# Fan_testing_rig.net
KiCad netlist of a schematic drawn in EasyEDA
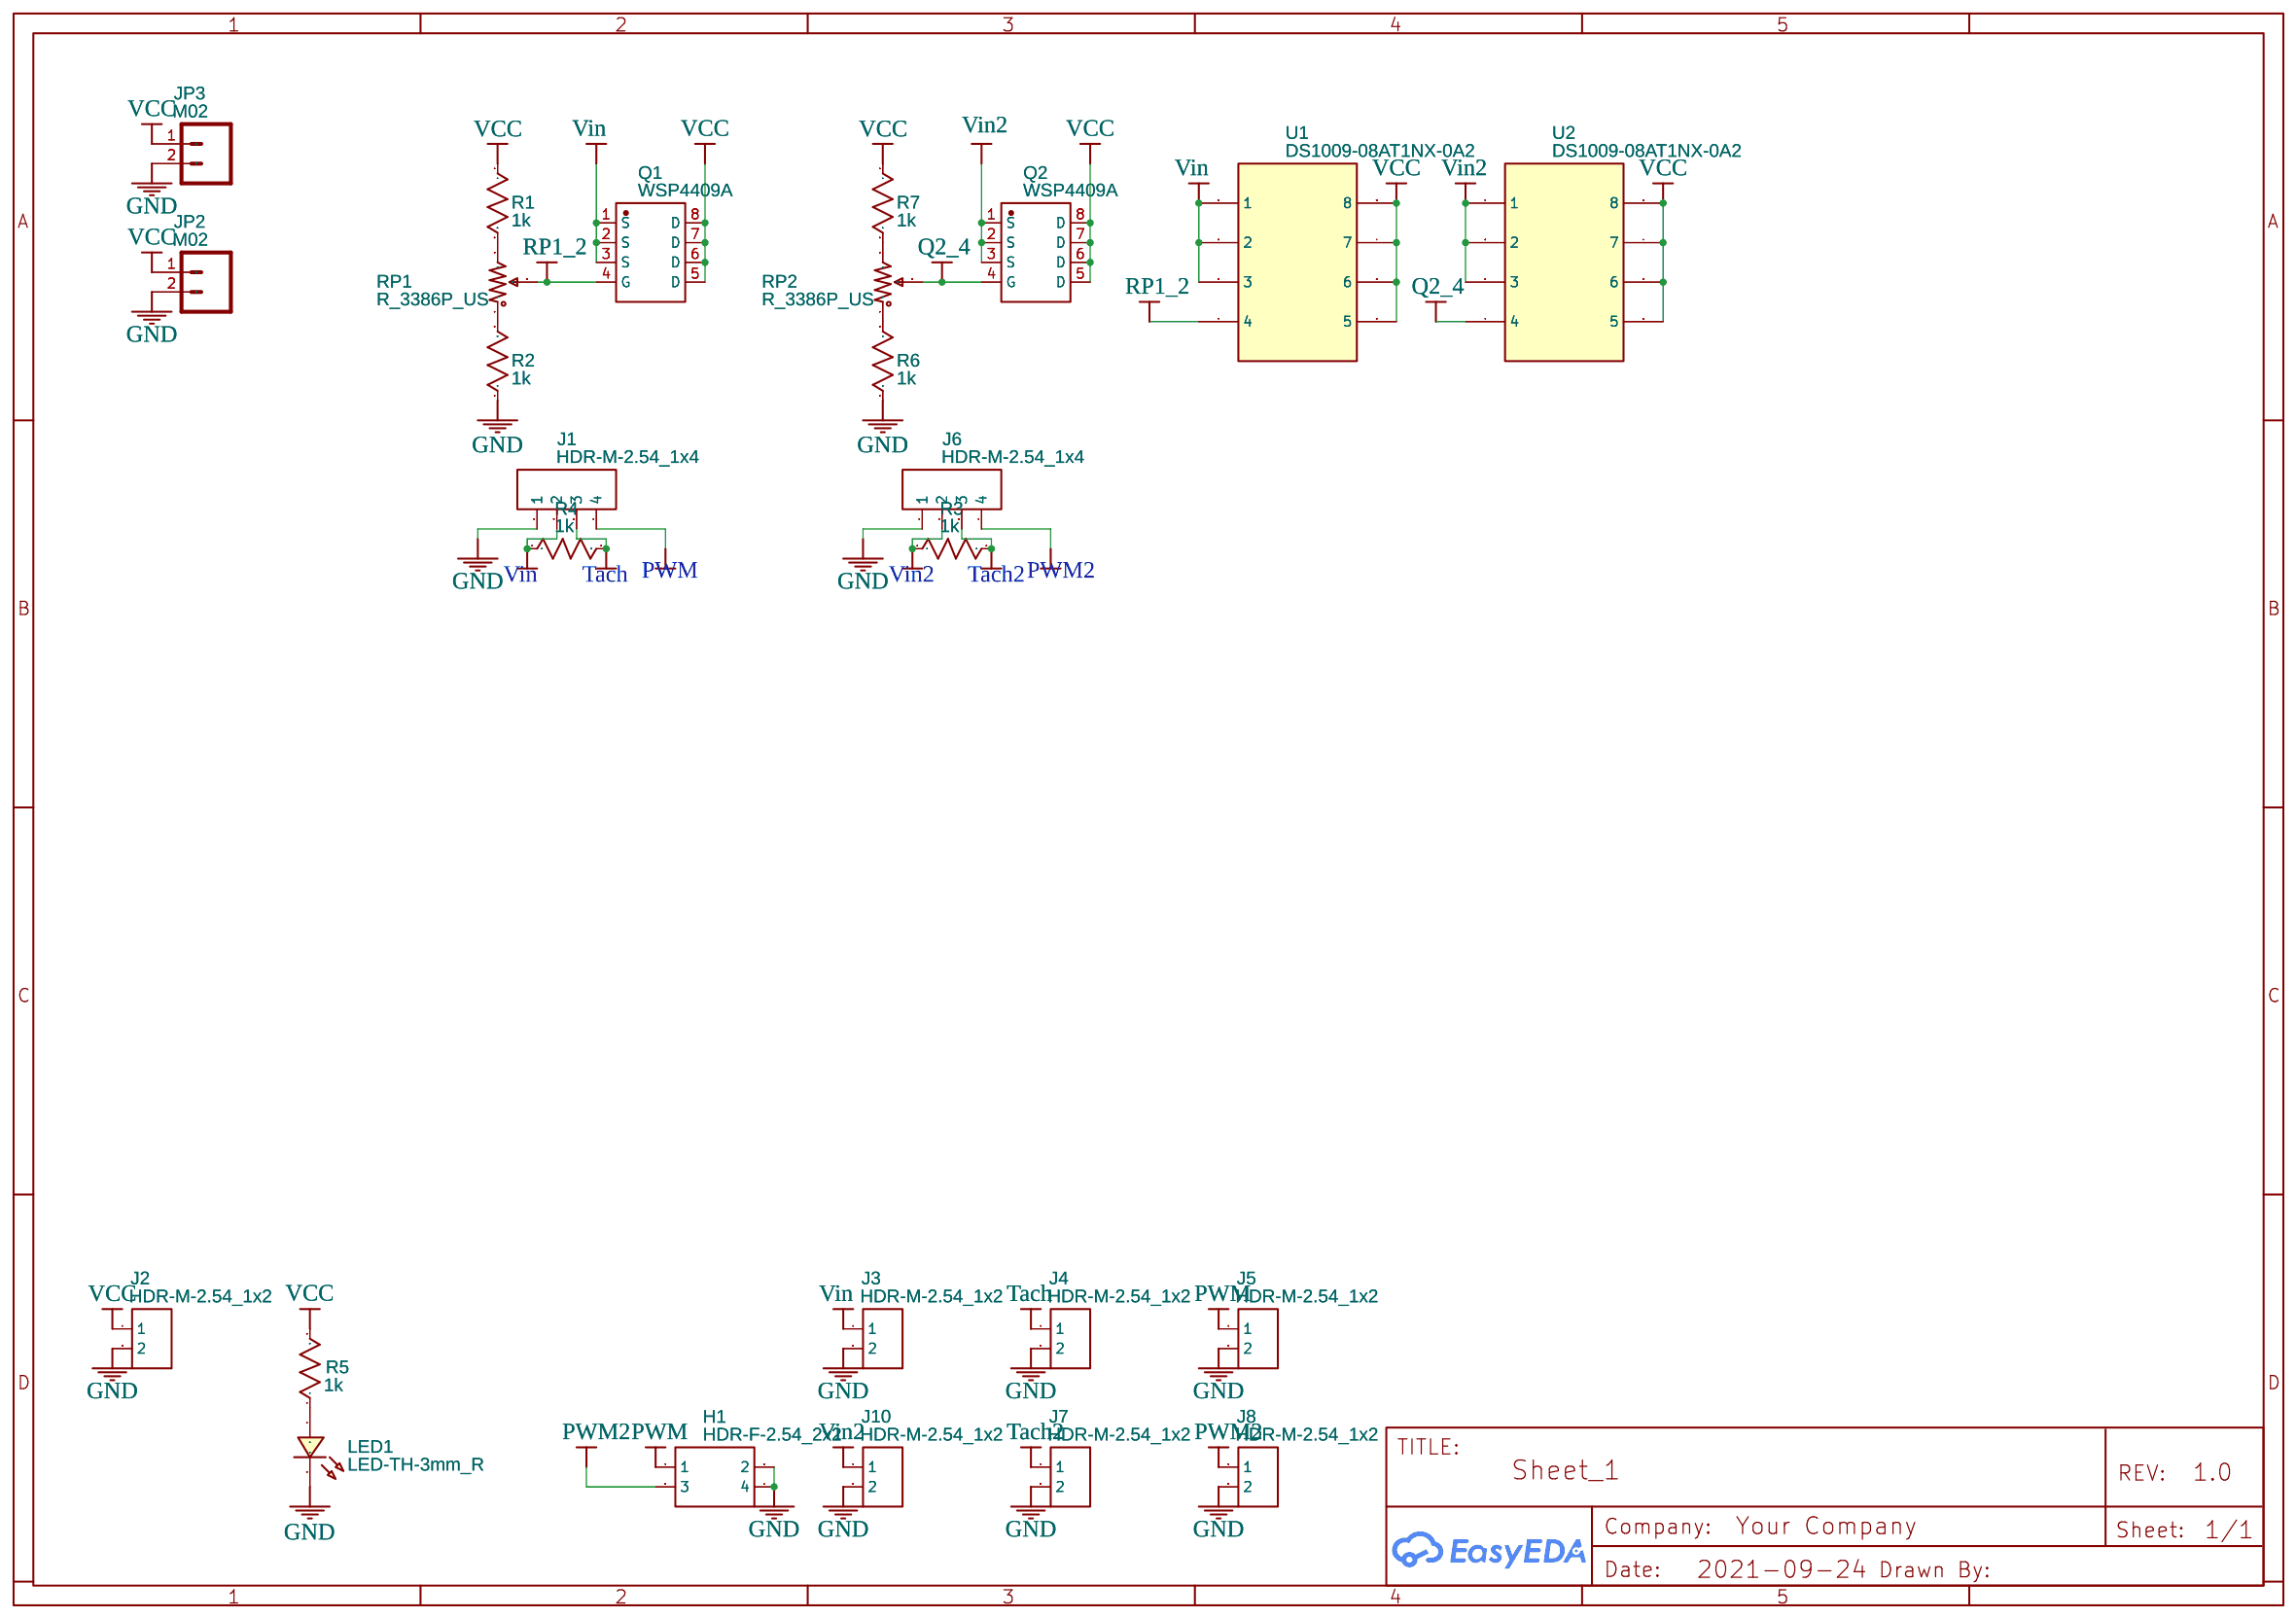
[diagram p0: main unit]
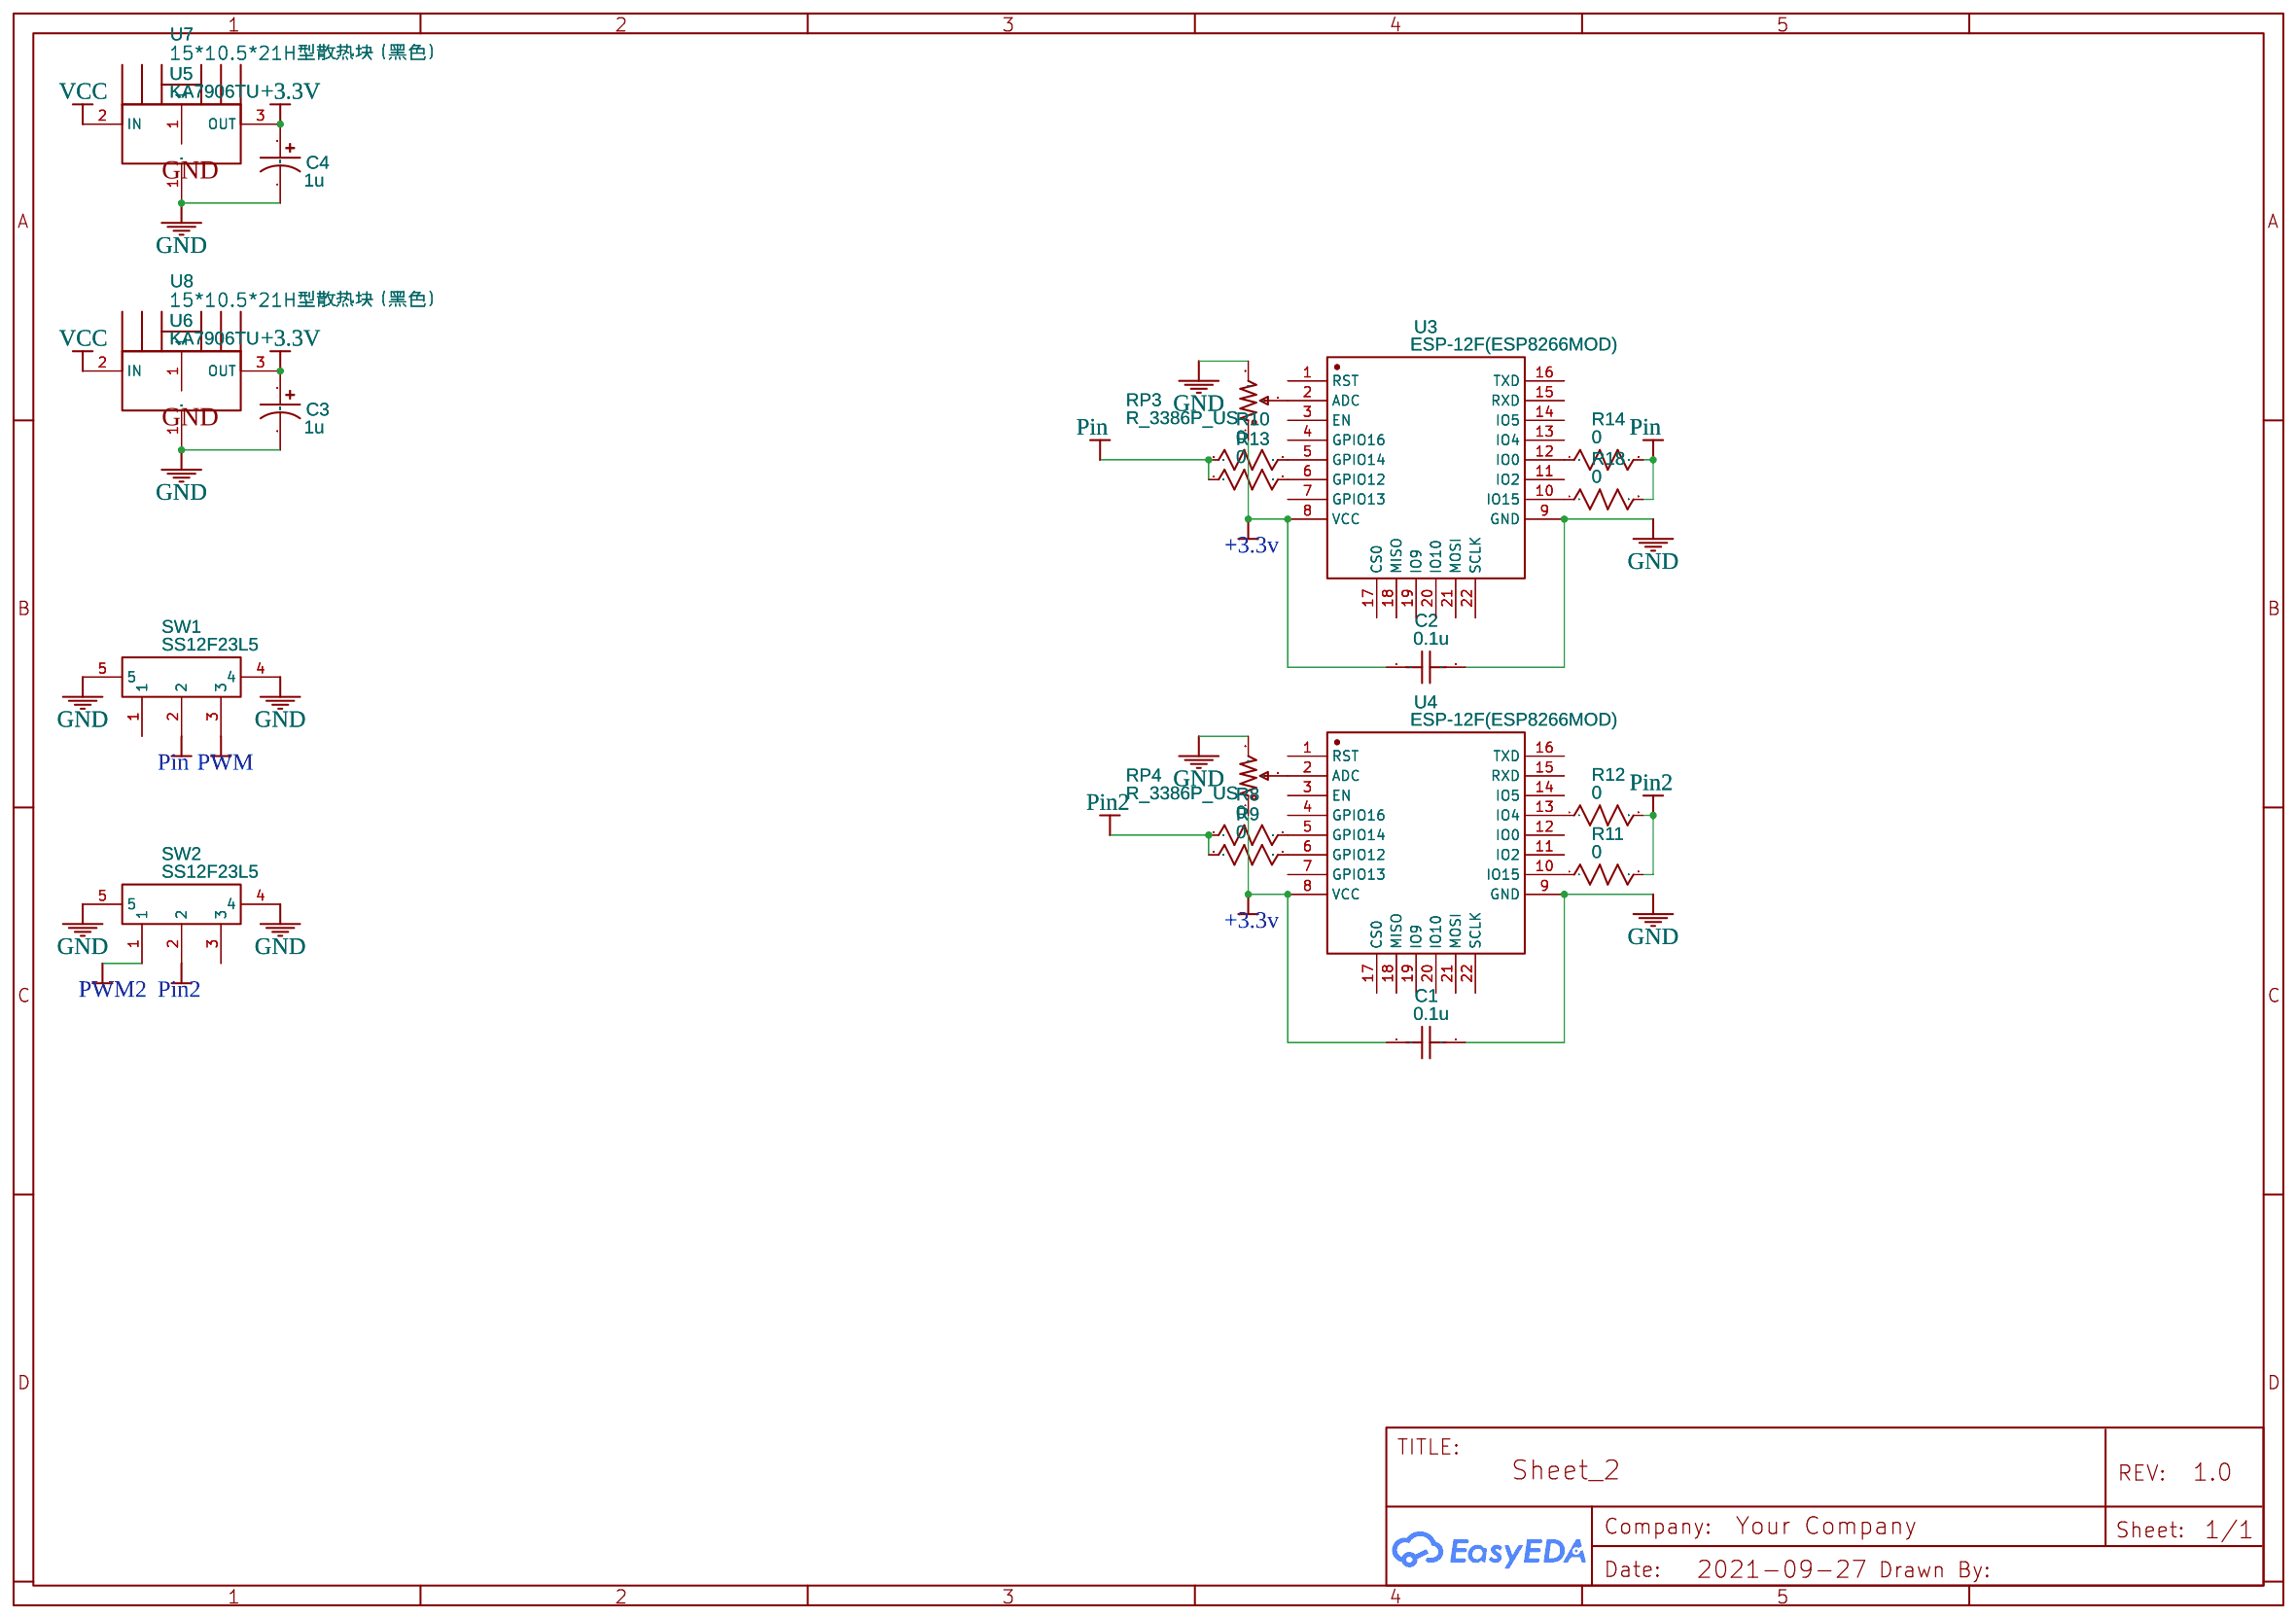
[diagram p1: PWM controll]

(export (version "E")
  (design (tool "Eeschema 10.0.6"))
  (components
    (comp (ref "H1")
      (value "HDR-F-2.54_2x2")
      (fields (field (name "BOM_Supplier Part") "C239342"))
      (libsource (lib "") (part "HDR-F-2.54_2x2"))
    )
    (comp (ref "J1")
      (value "HDR-M-2.54_1x4")
      (fields (field (name "BOM_Supplier Part") "C124378"))
      (libsource (lib "") (part "HDR-M-2.54_1x4"))
    )
    (comp (ref "J2")
      (value "HDR-M-2.54_1x2")
      (fields (field (name "BOM_Supplier Part") "C124375"))
      (libsource (lib "") (part "HDR-M-2.54_1x2"))
    )
    (comp (ref "J3")
      (value "HDR-M-2.54_1x2")
      (fields (field (name "BOM_Supplier Part") "C124375"))
      (libsource (lib "") (part "HDR-M-2.54_1x2"))
    )
    (comp (ref "J4")
      (value "HDR-M-2.54_1x2")
      (fields (field (name "BOM_Supplier Part") "C124375"))
      (libsource (lib "") (part "HDR-M-2.54_1x2"))
    )
    (comp (ref "J5")
      (value "HDR-M-2.54_1x2")
      (fields (field (name "BOM_Supplier Part") "C124375"))
      (libsource (lib "") (part "HDR-M-2.54_1x2"))
    )
    (comp (ref "J6")
      (value "HDR-M-2.54_1x4")
      (fields (field (name "BOM_Supplier Part") "C124378"))
      (libsource (lib "") (part "HDR-M-2.54_1x4"))
    )
    (comp (ref "J7")
      (value "HDR-M-2.54_1x2")
      (fields (field (name "BOM_Supplier Part") "C124375"))
      (libsource (lib "") (part "HDR-M-2.54_1x2"))
    )
    (comp (ref "J8")
      (value "HDR-M-2.54_1x2")
      (fields (field (name "BOM_Supplier Part") "C124375"))
      (libsource (lib "") (part "HDR-M-2.54_1x2"))
    )
    (comp (ref "J10")
      (value "HDR-M-2.54_1x2")
      (fields (field (name "BOM_Supplier Part") "C124375"))
      (libsource (lib "") (part "HDR-M-2.54_1x2"))
    )
    (comp (ref "JP2") (value "M02") (libsource (lib "") (part "M02")))
    (comp (ref "JP3") (value "M02") (libsource (lib "") (part "M02")))
    (comp (ref "LED1")
      (value "LED-TH-3mm_R")
      (fields
        (field (name "BOM_Manufacturer Part") "204-10SDRD/S530-A3-L")
        (field (name "BOM_Supplier Part") "C84774")
      )
      (libsource (lib "") (part "LED-TH-3mm_R"))
    )
    (comp (ref "Q1")
      (value "WSP4409A")
      (fields (field (name "BOM_Supplier Part") "C2880527"))
      (libsource (lib "") (part "WSP4409A"))
    )
    (comp (ref "Q2")
      (value "WSP4409A")
      (fields (field (name "BOM_Supplier Part") "C2880527"))
      (libsource (lib "") (part "WSP4409A"))
    )
    (comp (ref "R1") (value "1k") (libsource (lib "") (part "R_AXIAL-0.3_US")))
    (comp (ref "R2") (value "1k") (libsource (lib "") (part "R_AXIAL-0.3_US_1")))
    (comp (ref "R3") (value "1k") (libsource (lib "") (part "R_AXIAL-0.3_US_2")))
    (comp (ref "R4") (value "1k") (libsource (lib "") (part "R_AXIAL-0.3_US_2")))
    (comp (ref "R5") (value "1k") (libsource (lib "") (part "R_AXIAL-0.3_US_1")))
    (comp (ref "R6") (value "1k") (libsource (lib "") (part "R_AXIAL-0.3_US_1")))
    (comp (ref "R7") (value "1k") (libsource (lib "") (part "R_AXIAL-0.3_US")))
    (comp (ref "RP1") (value "R_3386P_US") (libsource (lib "") (part "R_3386P_US")))
    (comp (ref "RP2") (value "R_3386P_US") (libsource (lib "") (part "R_3386P_US")))
    (comp (ref "U1")
      (value "DS1009-08AT1NX-0A2")
      (fields (field (name "BOM_Supplier Part") "C72124"))
      (libsource (lib "") (part "DS1009-08AT1NX-0A2"))
    )
    (comp (ref "U2")
      (value "DS1009-08AT1NX-0A2")
      (fields (field (name "BOM_Supplier Part") "C72124"))
      (libsource (lib "") (part "DS1009-08AT1NX-0A2"))
    )
    (comp (ref "C1") (value "0.1u") (libsource (lib "") (part "C_0805_US")))
    (comp (ref "C2") (value "0.1u") (libsource (lib "") (part "C_0805_US")))
    (comp (ref "C3") (value "1u") (libsource (lib "") (part "CE_TH_D8.0×F3.5_US")))
    (comp (ref "C4") (value "1u") (libsource (lib "") (part "CE_TH_D8.0×F3.5_US")))
    (comp (ref "R8") (value "0") (libsource (lib "") (part "R_AXIAL-0.3_US")))
    (comp (ref "R9") (value "0") (libsource (lib "") (part "R_AXIAL-0.3_US")))
    (comp (ref "R10") (value "0") (libsource (lib "") (part "R_AXIAL-0.3_US")))
    (comp (ref "R11") (value "0") (libsource (lib "") (part "R_AXIAL-0.3_US")))
    (comp (ref "R12") (value "0") (libsource (lib "") (part "R_AXIAL-0.3_US")))
    (comp (ref "R13") (value "0") (libsource (lib "") (part "R_AXIAL-0.3_US")))
    (comp (ref "R14") (value "0") (libsource (lib "") (part "R_AXIAL-0.3_US")))
    (comp (ref "R18") (value "0") (libsource (lib "") (part "R_AXIAL-0.3_US")))
    (comp (ref "RP3") (value "R_3386P_US") (libsource (lib "") (part "R_3386P_US")))
    (comp (ref "RP4") (value "R_3386P_US") (libsource (lib "") (part "R_3386P_US")))
    (comp (ref "SW1")
      (value "SS12F23L5")
      (fields (field (name "BOM_Supplier Part") "C2884749"))
      (libsource (lib "") (part "SS12F23L5"))
    )
    (comp (ref "SW2")
      (value "SS12F23L5")
      (fields (field (name "BOM_Supplier Part") "C2884749"))
      (libsource (lib "") (part "SS12F23L5"))
    )
    (comp (ref "U3")
      (value "ESP-12F(ESP8266MOD)")
      (fields (field (name "BOM_Supplier Part") "C82891"))
      (libsource (lib "") (part "ESP-12F(ESP8266MOD)"))
    )
    (comp (ref "U4")
      (value "ESP-12F(ESP8266MOD)")
      (fields (field (name "BOM_Supplier Part") "C82891"))
      (libsource (lib "") (part "ESP-12F(ESP8266MOD)"))
    )
    (comp (ref "U5")
      (value "KA7906TU")
      (fields (field (name "BOM_Supplier Part") "C112610"))
      (libsource (lib "") (part "KA7906TU"))
    )
    (comp (ref "U6")
      (value "KA7906TU")
      (fields (field (name "BOM_Supplier Part") "C112610"))
      (libsource (lib "") (part "KA7906TU"))
    )
    (comp (ref "U7")
      (value "15*10.5*21H型散热块（黑色）")
      (fields (field (name "BOM_Supplier Part") "C116600"))
      (libsource (lib "") (part "15*10.5*21H型散热块（黑色）"))
    )
    (comp (ref "U8")
      (value "15*10.5*21H型散热块（黑色）")
      (fields (field (name "BOM_Supplier Part") "C116600"))
      (libsource (lib "") (part "15*10.5*21H型散热块（黑色）"))
    )
  )
  (nets
    (net (code "1") (name "+3.3V") (class "Default")
      (node (ref "C3") (pin "1") (pinfunction "1_1") (pintype "unspecified"))
      (node (ref "C4") (pin "1") (pinfunction "1_1") (pintype "unspecified"))
      (node (ref "U5") (pin "3") (pinfunction "OUT_3") (pintype "passive"))
      (node (ref "U6") (pin "3") (pinfunction "OUT_3") (pintype "passive"))
    )
    (net (code "2") (name "+3.3v") (class "Default")
      (node (ref "C1") (pin "1") (pinfunction "1_1") (pintype "unspecified"))
      (node (ref "C2") (pin "1") (pinfunction "1_1") (pintype "unspecified"))
      (node (ref "RP3") (pin "1") (pinfunction "1_1") (pintype "unspecified"))
      (node (ref "RP4") (pin "1") (pinfunction "1_1") (pintype "unspecified"))
      (node (ref "U3") (pin "8") (pinfunction "VCC_8") (pintype "unspecified"))
      (node (ref "U4") (pin "8") (pinfunction "VCC_8") (pintype "unspecified"))
    )
    (net (code "3") (name "GND") (class "Default")
      (node (ref "C1") (pin "2") (pinfunction "2_2") (pintype "unspecified"))
      (node (ref "C2") (pin "2") (pinfunction "2_2") (pintype "unspecified"))
      (node (ref "C3") (pin "2") (pinfunction "2_2") (pintype "unspecified"))
      (node (ref "C4") (pin "2") (pinfunction "2_2") (pintype "unspecified"))
      (node (ref "H1") (pin "2") (pinfunction "2_2") (pintype "unspecified"))
      (node (ref "H1") (pin "4") (pinfunction "4_4") (pintype "unspecified"))
      (node (ref "J1") (pin "1") (pinfunction "1_1") (pintype "unspecified"))
      (node (ref "J10") (pin "2") (pinfunction "2_2") (pintype "unspecified"))
      (node (ref "J2") (pin "2") (pinfunction "2_2") (pintype "unspecified"))
      (node (ref "J3") (pin "2") (pinfunction "2_2") (pintype "unspecified"))
      (node (ref "J4") (pin "2") (pinfunction "2_2") (pintype "unspecified"))
      (node (ref "J5") (pin "2") (pinfunction "2_2") (pintype "unspecified"))
      (node (ref "J6") (pin "1") (pinfunction "1_1") (pintype "unspecified"))
      (node (ref "J7") (pin "2") (pinfunction "2_2") (pintype "unspecified"))
      (node (ref "J8") (pin "2") (pinfunction "2_2") (pintype "unspecified"))
      (node (ref "JP2") (pin "2") (pinfunction "2_2") (pintype "unspecified"))
      (node (ref "JP3") (pin "2") (pinfunction "2_2") (pintype "unspecified"))
      (node (ref "LED1") (pin "2") (pinfunction "2_2") (pintype "unspecified"))
      (node (ref "R2") (pin "1") (pinfunction "1_1") (pintype "unspecified"))
      (node (ref "R6") (pin "1") (pinfunction "1_1") (pintype "unspecified"))
      (node (ref "RP3") (pin "3") (pinfunction "3_3") (pintype "unspecified"))
      (node (ref "RP4") (pin "3") (pinfunction "3_3") (pintype "unspecified"))
      (node (ref "SW1") (pin "4") (pinfunction "4_4") (pintype "unspecified"))
      (node (ref "SW1") (pin "5") (pinfunction "5_5") (pintype "unspecified"))
      (node (ref "SW2") (pin "4") (pinfunction "4_4") (pintype "unspecified"))
      (node (ref "SW2") (pin "5") (pinfunction "5_5") (pintype "unspecified"))
      (node (ref "U3") (pin "9") (pinfunction "GND_9") (pintype "unspecified"))
      (node (ref "U4") (pin "9") (pinfunction "GND_9") (pintype "unspecified"))
      (node (ref "U5") (pin "1") (pinfunction "GND_1") (pintype "passive"))
      (node (ref "U6") (pin "1") (pinfunction "GND_1") (pintype "passive"))
    )
    (net (code "4") (name "Net-(LED1-Pad1)") (class "Default")
      (node (ref "LED1") (pin "1") (pinfunction "1_1") (pintype "unspecified"))
      (node (ref "R5") (pin "1") (pinfunction "1_1") (pintype "unspecified"))
    )
    (net (code "5") (name "Net-(R1-Pad2)") (class "Default")
      (node (ref "R1") (pin "2") (pinfunction "2_2") (pintype "unspecified"))
      (node (ref "RP1") (pin "3") (pinfunction "3_3") (pintype "unspecified"))
    )
    (net (code "6") (name "Net-(R2-Pad2)") (class "Default")
      (node (ref "R2") (pin "2") (pinfunction "2_2") (pintype "unspecified"))
      (node (ref "RP1") (pin "1") (pinfunction "1_1") (pintype "unspecified"))
    )
    (net (code "7") (name "Net-(R6-Pad2)") (class "Default")
      (node (ref "R6") (pin "2") (pinfunction "2_2") (pintype "unspecified"))
      (node (ref "RP2") (pin "1") (pinfunction "1_1") (pintype "unspecified"))
    )
    (net (code "8") (name "Net-(R7-Pad2)") (class "Default")
      (node (ref "R7") (pin "2") (pinfunction "2_2") (pintype "unspecified"))
      (node (ref "RP2") (pin "3") (pinfunction "3_3") (pintype "unspecified"))
    )
    (net (code "9") (name "Net-(U3-ADC)") (class "Default")
      (node (ref "RP3") (pin "2") (pinfunction "2_2") (pintype "unspecified"))
      (node (ref "U3") (pin "2") (pinfunction "ADC_2") (pintype "unspecified"))
    )
    (net (code "10") (name "Net-(U3-GPIO12)") (class "Default")
      (node (ref "R13") (pin "2") (pinfunction "2_2") (pintype "unspecified"))
      (node (ref "U3") (pin "6") (pinfunction "GPIO12_6") (pintype "unspecified"))
    )
    (net (code "11") (name "Net-(U3-GPIO14)") (class "Default")
      (node (ref "R10") (pin "2") (pinfunction "2_2") (pintype "unspecified"))
      (node (ref "U3") (pin "5") (pinfunction "GPIO14_5") (pintype "unspecified"))
    )
    (net (code "12") (name "Net-(U3-IO0)") (class "Default")
      (node (ref "R14") (pin "1") (pinfunction "1_1") (pintype "unspecified"))
      (node (ref "U3") (pin "12") (pinfunction "IO0_12") (pintype "unspecified"))
    )
    (net (code "13") (name "Net-(U3-IO15)") (class "Default")
      (node (ref "R18") (pin "1") (pinfunction "1_1") (pintype "unspecified"))
      (node (ref "U3") (pin "10") (pinfunction "IO15_10") (pintype "unspecified"))
    )
    (net (code "14") (name "Net-(U4-ADC)") (class "Default")
      (node (ref "RP4") (pin "2") (pinfunction "2_2") (pintype "unspecified"))
      (node (ref "U4") (pin "2") (pinfunction "ADC_2") (pintype "unspecified"))
    )
    (net (code "15") (name "Net-(U4-GPIO12)") (class "Default")
      (node (ref "R9") (pin "2") (pinfunction "2_2") (pintype "unspecified"))
      (node (ref "U4") (pin "6") (pinfunction "GPIO12_6") (pintype "unspecified"))
    )
    (net (code "16") (name "Net-(U4-GPIO14)") (class "Default")
      (node (ref "R8") (pin "2") (pinfunction "2_2") (pintype "unspecified"))
      (node (ref "U4") (pin "5") (pinfunction "GPIO14_5") (pintype "unspecified"))
    )
    (net (code "17") (name "Net-(U4-IO4)") (class "Default")
      (node (ref "R12") (pin "1") (pinfunction "1_1") (pintype "unspecified"))
      (node (ref "U4") (pin "13") (pinfunction "IO4_13") (pintype "unspecified"))
    )
    (net (code "18") (name "Net-(U4-IO15)") (class "Default")
      (node (ref "R11") (pin "1") (pinfunction "1_1") (pintype "unspecified"))
      (node (ref "U4") (pin "10") (pinfunction "IO15_10") (pintype "unspecified"))
    )
    (net (code "19") (name "PWM") (class "Default")
      (node (ref "H1") (pin "1") (pinfunction "1_1") (pintype "unspecified"))
      (node (ref "J1") (pin "4") (pinfunction "4_4") (pintype "unspecified"))
      (node (ref "J5") (pin "1") (pinfunction "1_1") (pintype "unspecified"))
      (node (ref "SW1") (pin "3") (pinfunction "3_3") (pintype "unspecified"))
    )
    (net (code "20") (name "PWM2") (class "Default")
      (node (ref "H1") (pin "3") (pinfunction "3_3") (pintype "unspecified"))
      (node (ref "J6") (pin "4") (pinfunction "4_4") (pintype "unspecified"))
      (node (ref "J8") (pin "1") (pinfunction "1_1") (pintype "unspecified"))
      (node (ref "SW2") (pin "1") (pinfunction "1_1") (pintype "unspecified"))
    )
    (net (code "21") (name "Pin") (class "Default")
      (node (ref "R10") (pin "1") (pinfunction "1_1") (pintype "unspecified"))
      (node (ref "R13") (pin "1") (pinfunction "1_1") (pintype "unspecified"))
      (node (ref "R14") (pin "2") (pinfunction "2_2") (pintype "unspecified"))
      (node (ref "R18") (pin "2") (pinfunction "2_2") (pintype "unspecified"))
      (node (ref "SW1") (pin "2") (pinfunction "2_2") (pintype "unspecified"))
    )
    (net (code "22") (name "Pin2") (class "Default")
      (node (ref "R11") (pin "2") (pinfunction "2_2") (pintype "unspecified"))
      (node (ref "R12") (pin "2") (pinfunction "2_2") (pintype "unspecified"))
      (node (ref "R8") (pin "1") (pinfunction "1_1") (pintype "unspecified"))
      (node (ref "R9") (pin "1") (pinfunction "1_1") (pintype "unspecified"))
      (node (ref "SW2") (pin "2") (pinfunction "2_2") (pintype "unspecified"))
    )
    (net (code "23") (name "Q2_4") (class "Default")
      (node (ref "Q2") (pin "4") (pinfunction "G_4") (pintype "unspecified"))
      (node (ref "RP2") (pin "2") (pinfunction "2_2") (pintype "unspecified"))
      (node (ref "U2") (pin "4") (pinfunction "4_4") (pintype "input"))
    )
    (net (code "24") (name "RP1_2") (class "Default")
      (node (ref "Q1") (pin "4") (pinfunction "G_4") (pintype "unspecified"))
      (node (ref "RP1") (pin "2") (pinfunction "2_2") (pintype "unspecified"))
      (node (ref "U1") (pin "4") (pinfunction "4_4") (pintype "input"))
    )
    (net (code "25") (name "Tach") (class "Default")
      (node (ref "J1") (pin "3") (pinfunction "3_3") (pintype "unspecified"))
      (node (ref "J4") (pin "1") (pinfunction "1_1") (pintype "unspecified"))
      (node (ref "R4") (pin "2") (pinfunction "2_2") (pintype "unspecified"))
    )
    (net (code "26") (name "Tach2") (class "Default")
      (node (ref "J6") (pin "3") (pinfunction "3_3") (pintype "unspecified"))
      (node (ref "J7") (pin "1") (pinfunction "1_1") (pintype "unspecified"))
      (node (ref "R3") (pin "2") (pinfunction "2_2") (pintype "unspecified"))
    )
    (net (code "27") (name "VCC") (class "Default")
      (node (ref "J2") (pin "1") (pinfunction "1_1") (pintype "unspecified"))
      (node (ref "JP2") (pin "1") (pinfunction "1_1") (pintype "unspecified"))
      (node (ref "JP3") (pin "1") (pinfunction "1_1") (pintype "unspecified"))
      (node (ref "Q1") (pin "5") (pinfunction "D_5") (pintype "unspecified"))
      (node (ref "Q1") (pin "6") (pinfunction "D_6") (pintype "unspecified"))
      (node (ref "Q1") (pin "7") (pinfunction "D_7") (pintype "unspecified"))
      (node (ref "Q1") (pin "8") (pinfunction "D_8") (pintype "unspecified"))
      (node (ref "Q2") (pin "5") (pinfunction "D_5") (pintype "unspecified"))
      (node (ref "Q2") (pin "6") (pinfunction "D_6") (pintype "unspecified"))
      (node (ref "Q2") (pin "7") (pinfunction "D_7") (pintype "unspecified"))
      (node (ref "Q2") (pin "8") (pinfunction "D_8") (pintype "unspecified"))
      (node (ref "R1") (pin "1") (pinfunction "1_1") (pintype "unspecified"))
      (node (ref "R5") (pin "2") (pinfunction "2_2") (pintype "unspecified"))
      (node (ref "R7") (pin "1") (pinfunction "1_1") (pintype "unspecified"))
      (node (ref "U1") (pin "5") (pinfunction "5_5") (pintype "input"))
      (node (ref "U1") (pin "6") (pinfunction "6_6") (pintype "input"))
      (node (ref "U1") (pin "7") (pinfunction "7_7") (pintype "input"))
      (node (ref "U1") (pin "8") (pinfunction "8_8") (pintype "input"))
      (node (ref "U2") (pin "5") (pinfunction "5_5") (pintype "input"))
      (node (ref "U2") (pin "6") (pinfunction "6_6") (pintype "input"))
      (node (ref "U2") (pin "7") (pinfunction "7_7") (pintype "input"))
      (node (ref "U2") (pin "8") (pinfunction "8_8") (pintype "input"))
      (node (ref "U5") (pin "2") (pinfunction "IN_2") (pintype "passive"))
      (node (ref "U6") (pin "2") (pinfunction "IN_2") (pintype "passive"))
    )
    (net (code "28") (name "Vin") (class "Default")
      (node (ref "J1") (pin "2") (pinfunction "2_2") (pintype "unspecified"))
      (node (ref "J3") (pin "1") (pinfunction "1_1") (pintype "unspecified"))
      (node (ref "Q1") (pin "1") (pinfunction "S_1") (pintype "unspecified"))
      (node (ref "Q1") (pin "2") (pinfunction "S_2") (pintype "unspecified"))
      (node (ref "Q1") (pin "3") (pinfunction "S_3") (pintype "unspecified"))
      (node (ref "R4") (pin "1") (pinfunction "1_1") (pintype "unspecified"))
      (node (ref "U1") (pin "1") (pinfunction "1_1") (pintype "input"))
      (node (ref "U1") (pin "2") (pinfunction "2_2") (pintype "input"))
      (node (ref "U1") (pin "3") (pinfunction "3_3") (pintype "input"))
    )
    (net (code "29") (name "Vin2") (class "Default")
      (node (ref "J10") (pin "1") (pinfunction "1_1") (pintype "unspecified"))
      (node (ref "J6") (pin "2") (pinfunction "2_2") (pintype "unspecified"))
      (node (ref "Q2") (pin "1") (pinfunction "S_1") (pintype "unspecified"))
      (node (ref "Q2") (pin "2") (pinfunction "S_2") (pintype "unspecified"))
      (node (ref "Q2") (pin "3") (pinfunction "S_3") (pintype "unspecified"))
      (node (ref "R3") (pin "1") (pinfunction "1_1") (pintype "unspecified"))
      (node (ref "U2") (pin "1") (pinfunction "1_1") (pintype "input"))
      (node (ref "U2") (pin "2") (pinfunction "2_2") (pintype "input"))
      (node (ref "U2") (pin "3") (pinfunction "3_3") (pintype "input"))
    )
    (net (code "30") (name "unconnected-(SW1-Pad1)") (class "Default")
      (node (ref "SW1") (pin "1") (pinfunction "1_1") (pintype "unspecified"))
    )
    (net (code "31") (name "unconnected-(SW2-Pad3)") (class "Default")
      (node (ref "SW2") (pin "3") (pinfunction "3_3") (pintype "unspecified"))
    )
    (net (code "32") (name "unconnected-(U3-CS0-Pad17)") (class "Default")
      (node (ref "U3") (pin "17") (pinfunction "CS0_17") (pintype "unspecified"))
    )
    (net (code "33") (name "unconnected-(U3-EN-Pad3)") (class "Default")
      (node (ref "U3") (pin "3") (pinfunction "EN_3") (pintype "unspecified"))
    )
    (net (code "34") (name "unconnected-(U3-GPIO13-Pad7)") (class "Default")
      (node (ref "U3") (pin "7") (pinfunction "GPIO13_7") (pintype "unspecified"))
    )
    (net (code "35") (name "unconnected-(U3-GPIO16-Pad4)") (class "Default")
      (node (ref "U3") (pin "4") (pinfunction "GPIO16_4") (pintype "unspecified"))
    )
    (net (code "36") (name "unconnected-(U3-IO2-Pad11)") (class "Default")
      (node (ref "U3") (pin "11") (pinfunction "IO2_11") (pintype "unspecified"))
    )
    (net (code "37") (name "unconnected-(U3-IO4-Pad13)") (class "Default")
      (node (ref "U3") (pin "13") (pinfunction "IO4_13") (pintype "unspecified"))
    )
    (net (code "38") (name "unconnected-(U3-IO5-Pad14)") (class "Default")
      (node (ref "U3") (pin "14") (pinfunction "IO5_14") (pintype "unspecified"))
    )
    (net (code "39") (name "unconnected-(U3-IO9-Pad19)") (class "Default")
      (node (ref "U3") (pin "19") (pinfunction "IO9_19") (pintype "unspecified"))
    )
    (net (code "40") (name "unconnected-(U3-IO10-Pad20)") (class "Default")
      (node (ref "U3") (pin "20") (pinfunction "IO10_20") (pintype "unspecified"))
    )
    (net (code "41") (name "unconnected-(U3-MISO-Pad18)") (class "Default")
      (node (ref "U3") (pin "18") (pinfunction "MISO_18") (pintype "unspecified"))
    )
    (net (code "42") (name "unconnected-(U3-MOSI-Pad21)") (class "Default")
      (node (ref "U3") (pin "21") (pinfunction "MOSI_21") (pintype "unspecified"))
    )
    (net (code "43") (name "unconnected-(U3-RST-Pad1)") (class "Default")
      (node (ref "U3") (pin "1") (pinfunction "RST_1") (pintype "unspecified"))
    )
    (net (code "44") (name "unconnected-(U3-RXD-Pad15)") (class "Default")
      (node (ref "U3") (pin "15") (pinfunction "RXD_15") (pintype "unspecified"))
    )
    (net (code "45") (name "unconnected-(U3-SCLK-Pad22)") (class "Default")
      (node (ref "U3") (pin "22") (pinfunction "SCLK_22") (pintype "unspecified"))
    )
    (net (code "46") (name "unconnected-(U3-TXD-Pad16)") (class "Default")
      (node (ref "U3") (pin "16") (pinfunction "TXD_16") (pintype "unspecified"))
    )
    (net (code "47") (name "unconnected-(U4-CS0-Pad17)") (class "Default")
      (node (ref "U4") (pin "17") (pinfunction "CS0_17") (pintype "unspecified"))
    )
    (net (code "48") (name "unconnected-(U4-EN-Pad3)") (class "Default")
      (node (ref "U4") (pin "3") (pinfunction "EN_3") (pintype "unspecified"))
    )
    (net (code "49") (name "unconnected-(U4-GPIO13-Pad7)") (class "Default")
      (node (ref "U4") (pin "7") (pinfunction "GPIO13_7") (pintype "unspecified"))
    )
    (net (code "50") (name "unconnected-(U4-GPIO16-Pad4)") (class "Default")
      (node (ref "U4") (pin "4") (pinfunction "GPIO16_4") (pintype "unspecified"))
    )
    (net (code "51") (name "unconnected-(U4-IO0-Pad12)") (class "Default")
      (node (ref "U4") (pin "12") (pinfunction "IO0_12") (pintype "unspecified"))
    )
    (net (code "52") (name "unconnected-(U4-IO2-Pad11)") (class "Default")
      (node (ref "U4") (pin "11") (pinfunction "IO2_11") (pintype "unspecified"))
    )
    (net (code "53") (name "unconnected-(U4-IO5-Pad14)") (class "Default")
      (node (ref "U4") (pin "14") (pinfunction "IO5_14") (pintype "unspecified"))
    )
    (net (code "54") (name "unconnected-(U4-IO9-Pad19)") (class "Default")
      (node (ref "U4") (pin "19") (pinfunction "IO9_19") (pintype "unspecified"))
    )
    (net (code "55") (name "unconnected-(U4-IO10-Pad20)") (class "Default")
      (node (ref "U4") (pin "20") (pinfunction "IO10_20") (pintype "unspecified"))
    )
    (net (code "56") (name "unconnected-(U4-MISO-Pad18)") (class "Default")
      (node (ref "U4") (pin "18") (pinfunction "MISO_18") (pintype "unspecified"))
    )
    (net (code "57") (name "unconnected-(U4-MOSI-Pad21)") (class "Default")
      (node (ref "U4") (pin "21") (pinfunction "MOSI_21") (pintype "unspecified"))
    )
    (net (code "58") (name "unconnected-(U4-RST-Pad1)") (class "Default")
      (node (ref "U4") (pin "1") (pinfunction "RST_1") (pintype "unspecified"))
    )
    (net (code "59") (name "unconnected-(U4-RXD-Pad15)") (class "Default")
      (node (ref "U4") (pin "15") (pinfunction "RXD_15") (pintype "unspecified"))
    )
    (net (code "60") (name "unconnected-(U4-SCLK-Pad22)") (class "Default")
      (node (ref "U4") (pin "22") (pinfunction "SCLK_22") (pintype "unspecified"))
    )
    (net (code "61") (name "unconnected-(U4-TXD-Pad16)") (class "Default")
      (node (ref "U4") (pin "16") (pinfunction "TXD_16") (pintype "unspecified"))
    )
    (net (code "62") (name "unconnected-(U7-Pad1)") (class "Default")
      (node (ref "U7") (pin "1") (pinfunction "1_1") (pintype "unspecified"))
    )
    (net (code "63") (name "unconnected-(U8-Pad1)") (class "Default")
      (node (ref "U8") (pin "1") (pinfunction "1_1") (pintype "unspecified"))
    )
  )
)
